# PL9823-breakout-board.net
KiCad netlist of a schematic drawn in EAGLE
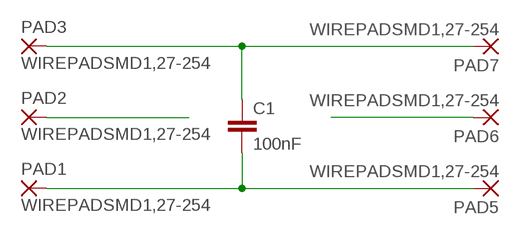
[diagram p0: schematic, sheet 1]

(export (version "E")
  (design (tool "Eeschema 10.0.6"))
  (components
    (comp (ref "C1")
      (value "100nF")
      (footprint "eagle-import:C0805K")
      (libsource (lib "eagle-import") (part "C-EUC0805K"))
    )
    (comp (ref "PAD1")
      (value "WIREPADSMD1,27-254")
      (footprint "eagle-import:SMD1,27-2,54")
      (libsource (lib "eagle-import") (part "WIREPADSMD1,27-254"))
    )
    (comp (ref "PAD2")
      (value "WIREPADSMD1,27-254")
      (footprint "eagle-import:SMD1,27-2,54")
      (libsource (lib "eagle-import") (part "WIREPADSMD1,27-254"))
    )
    (comp (ref "PAD3")
      (value "WIREPADSMD1,27-254")
      (footprint "eagle-import:SMD1,27-2,54")
      (libsource (lib "eagle-import") (part "WIREPADSMD1,27-254"))
    )
    (comp (ref "PAD5")
      (value "WIREPADSMD1,27-254")
      (footprint "eagle-import:SMD1,27-2,54")
      (libsource (lib "eagle-import") (part "WIREPADSMD1,27-254"))
    )
    (comp (ref "PAD6")
      (value "WIREPADSMD1,27-254")
      (footprint "eagle-import:SMD1,27-2,54")
      (libsource (lib "eagle-import") (part "WIREPADSMD1,27-254"))
    )
    (comp (ref "PAD7")
      (value "WIREPADSMD1,27-254")
      (footprint "eagle-import:SMD1,27-2,54")
      (libsource (lib "eagle-import") (part "WIREPADSMD1,27-254"))
    )
  )
  (nets
    (net (code "1") (name "Net-(PAD1-P)") (class "Default")
      (node (ref "C1") (pin "2") (pinfunction "2_2") (pintype "passive"))
      (node (ref "PAD1") (pin "1") (pinfunction "P_1") (pintype "passive"))
      (node (ref "PAD5") (pin "1") (pinfunction "P_1") (pintype "passive"))
    )
    (net (code "2") (name "Net-(PAD3-P)") (class "Default")
      (node (ref "C1") (pin "1") (pinfunction "1_1") (pintype "passive"))
      (node (ref "PAD3") (pin "1") (pinfunction "P_1") (pintype "passive"))
      (node (ref "PAD7") (pin "1") (pinfunction "P_1") (pintype "passive"))
    )
    (net (code "3") (name "unconnected-(PAD2-P-Pad1)") (class "Default")
      (node (ref "PAD2") (pin "1") (pinfunction "P_1") (pintype "passive"))
    )
    (net (code "4") (name "unconnected-(PAD6-P-Pad1)") (class "Default")
      (node (ref "PAD6") (pin "1") (pinfunction "P_1") (pintype "passive"))
    )
  )
)
